# GPS_Module.net
KiCad netlist of a schematic drawn in Altium Designer
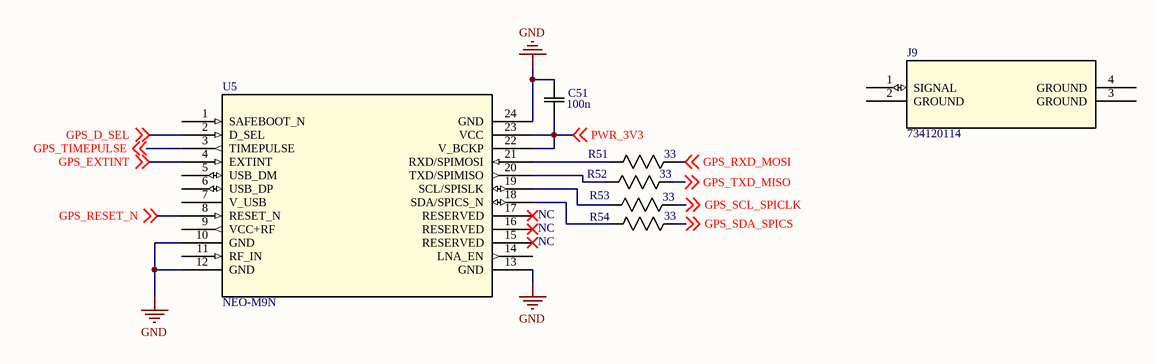
[diagram p0: GPS Module.SchDoc]

(export (version "E")
  (design (tool "Eeschema 10.0.6"))
  (components
    (comp (ref "C51")
      (value "100n")
      (footprint "YAG_CC0603_YAG")
      (description "No Description Available")
      (fields
        (field (name "MANUFACTURER_PART_NUMBER") "CC0603KRX7R8BB104")
        (field (name "COPYRIGHT") "Copyright (C) 2024 Ultra Librarian. All rights reserved.")
      )
      (libsource (lib "CC0603KRX7R8BB104") (part "CC0603KRX7R8BB104"))
    )
    (comp (ref "J9")
      (value "734120114")
      (footprint "73412-0114_MOL")
      (description "No Description Available")
      (libsource (lib "uFL") (part "734120114"))
    )
    (comp (ref "R51")
      (value "33")
      (footprint "RC0603N_VIS")
      (description "RES(10K, SMD-603)")
      (libsource (lib "CRCW060310K0JNEA") (part "RES(10K, SMD-603)"))
    )
    (comp (ref "R52")
      (value "33")
      (footprint "RC0603N_VIS")
      (description "RES(10K, SMD-603)")
      (libsource (lib "CRCW060310K0JNEA") (part "RES(10K, SMD-603)"))
    )
    (comp (ref "R53")
      (value "33")
      (footprint "RC0603N_VIS")
      (description "RES(10K, SMD-603)")
      (libsource (lib "CRCW060310K0JNEA") (part "RES(10K, SMD-603)"))
    )
    (comp (ref "R54")
      (value "33")
      (footprint "RC0603N_VIS")
      (description "RES(10K, SMD-603)")
      (libsource (lib "CRCW060310K0JNEA") (part "RES(10K, SMD-603)"))
    )
    (comp (ref "U5")
      (value "NEO-M9N")
      (footprint "NEO-M9N_UBL")
      (description "No Description Available")
      (libsource (lib "NEO-M9N") (part "NEO-M9N"))
    )
  )
  (nets
    (net (code "1") (name "GND") (class "Default")
      (node (ref "C51") (pin "2") (pinfunction "2_2") (pintype "passive"))
      (node (ref "U5") (pin "10") (pinfunction "GND_10") (pintype "power_in"))
      (node (ref "U5") (pin "12") (pinfunction "GND_12") (pintype "power_in"))
      (node (ref "U5") (pin "13") (pinfunction "GND_13") (pintype "power_in"))
      (node (ref "U5") (pin "24") (pinfunction "GND_24") (pintype "power_in"))
    )
    (net (code "2") (name "GPS_D_SEL") (class "Default")
      (node (ref "U5") (pin "2") (pinfunction "D_SEL_2") (pintype "input"))
    )
    (net (code "3") (name "GPS_EXTINT") (class "Default")
      (node (ref "U5") (pin "4") (pinfunction "EXTINT_4") (pintype "input"))
    )
    (net (code "4") (name "GPS_RESET_N") (class "Default")
      (node (ref "U5") (pin "8") (pinfunction "RESET_N_8") (pintype "input"))
    )
    (net (code "5") (name "GPS_RXD_MOSI") (class "Default")
      (node (ref "R51") (pin "2") (pinfunction "2_2") (pintype "passive"))
    )
    (net (code "6") (name "GPS_SCL_SPICLK") (class "Default")
      (node (ref "R53") (pin "2") (pinfunction "2_2") (pintype "passive"))
    )
    (net (code "7") (name "GPS_SDA_SPICS") (class "Default")
      (node (ref "R54") (pin "2") (pinfunction "2_2") (pintype "passive"))
    )
    (net (code "8") (name "GPS_TIMEPULSE") (class "Default")
      (node (ref "U5") (pin "3") (pinfunction "TIMEPULSE_3") (pintype "output"))
    )
    (net (code "9") (name "GPS_TXD_MISO") (class "Default")
      (node (ref "R52") (pin "2") (pinfunction "2_2") (pintype "passive"))
    )
    (net (code "10") (name "Net-(U5-RXD{slash}SPIMOSI)") (class "Default")
      (node (ref "R51") (pin "1") (pinfunction "1_1") (pintype "passive"))
      (node (ref "U5") (pin "21") (pinfunction "RXD/SPIMOSI_21") (pintype "input"))
    )
    (net (code "11") (name "Net-(U5-SCL{slash}SPISLK)") (class "Default")
      (node (ref "R53") (pin "1") (pinfunction "1_1") (pintype "passive"))
      (node (ref "U5") (pin "19") (pinfunction "SCL/SPISLK_19") (pintype "bidirectional"))
    )
    (net (code "12") (name "Net-(U5-SDA{slash}SPICS_N)") (class "Default")
      (node (ref "R54") (pin "1") (pinfunction "1_1") (pintype "passive"))
      (node (ref "U5") (pin "18") (pinfunction "SDA/SPICS_N_18") (pintype "bidirectional"))
    )
    (net (code "13") (name "Net-(U5-TXD{slash}SPIMISO)") (class "Default")
      (node (ref "R52") (pin "1") (pinfunction "1_1") (pintype "passive"))
      (node (ref "U5") (pin "20") (pinfunction "TXD/SPIMISO_20") (pintype "output"))
    )
    (net (code "14") (name "PWR_3V3") (class "Default")
      (node (ref "C51") (pin "1") (pinfunction "1_1") (pintype "passive"))
      (node (ref "U5") (pin "22") (pinfunction "V_BCKP_22") (pintype "power_in"))
      (node (ref "U5") (pin "23") (pinfunction "VCC_23") (pintype "power_in"))
    )
    (net (code "15") (name "unconnected-(J9-GROUND-Pad2)") (class "Default")
      (node (ref "J9") (pin "2") (pinfunction "GROUND_2") (pintype "power_in"))
    )
    (net (code "16") (name "unconnected-(J9-GROUND-Pad3)") (class "Default")
      (node (ref "J9") (pin "3") (pinfunction "GROUND_3") (pintype "power_in"))
    )
    (net (code "17") (name "unconnected-(J9-GROUND-Pad4)") (class "Default")
      (node (ref "J9") (pin "4") (pinfunction "GROUND_4") (pintype "power_in"))
    )
    (net (code "18") (name "unconnected-(J9-SIGNAL-Pad1)") (class "Default")
      (node (ref "J9") (pin "1") (pinfunction "SIGNAL_1") (pintype "bidirectional"))
    )
    (net (code "19") (name "unconnected-(U5-LNA_EN-Pad14)") (class "Default")
      (node (ref "U5") (pin "14") (pinfunction "LNA_EN_14") (pintype "output"))
    )
    (net (code "20") (name "unconnected-(U5-RESERVED-Pad15)") (class "Default")
      (node (ref "U5") (pin "15") (pinfunction "RESERVED_15") (pintype "passive+no_connect"))
    )
    (net (code "21") (name "unconnected-(U5-RESERVED-Pad16)") (class "Default")
      (node (ref "U5") (pin "16") (pinfunction "RESERVED_16") (pintype "passive+no_connect"))
    )
    (net (code "22") (name "unconnected-(U5-RESERVED-Pad17)") (class "Default")
      (node (ref "U5") (pin "17") (pinfunction "RESERVED_17") (pintype "passive+no_connect"))
    )
    (net (code "23") (name "unconnected-(U5-RF_IN-Pad11)") (class "Default")
      (node (ref "U5") (pin "11") (pinfunction "RF_IN_11") (pintype "input"))
    )
    (net (code "24") (name "unconnected-(U5-SAFEBOOT_N-Pad1)") (class "Default")
      (node (ref "U5") (pin "1") (pinfunction "SAFEBOOT_N_1") (pintype "input"))
    )
    (net (code "25") (name "unconnected-(U5-USB_DM-Pad5)") (class "Default")
      (node (ref "U5") (pin "5") (pinfunction "USB_DM_5") (pintype "bidirectional"))
    )
    (net (code "26") (name "unconnected-(U5-USB_DP-Pad6)") (class "Default")
      (node (ref "U5") (pin "6") (pinfunction "USB_DP_6") (pintype "bidirectional"))
    )
    (net (code "27") (name "unconnected-(U5-VCC+RF-Pad9)") (class "Default")
      (node (ref "U5") (pin "9") (pinfunction "VCC+RF_9") (pintype "output"))
    )
    (net (code "28") (name "unconnected-(U5-V_USB-Pad7)") (class "Default")
      (node (ref "U5") (pin "7") (pinfunction "V_USB_7") (pintype "power_in"))
    )
  )
)
